# SCH_SnailCard.net
KiCad netlist of a schematic drawn in EasyEDA
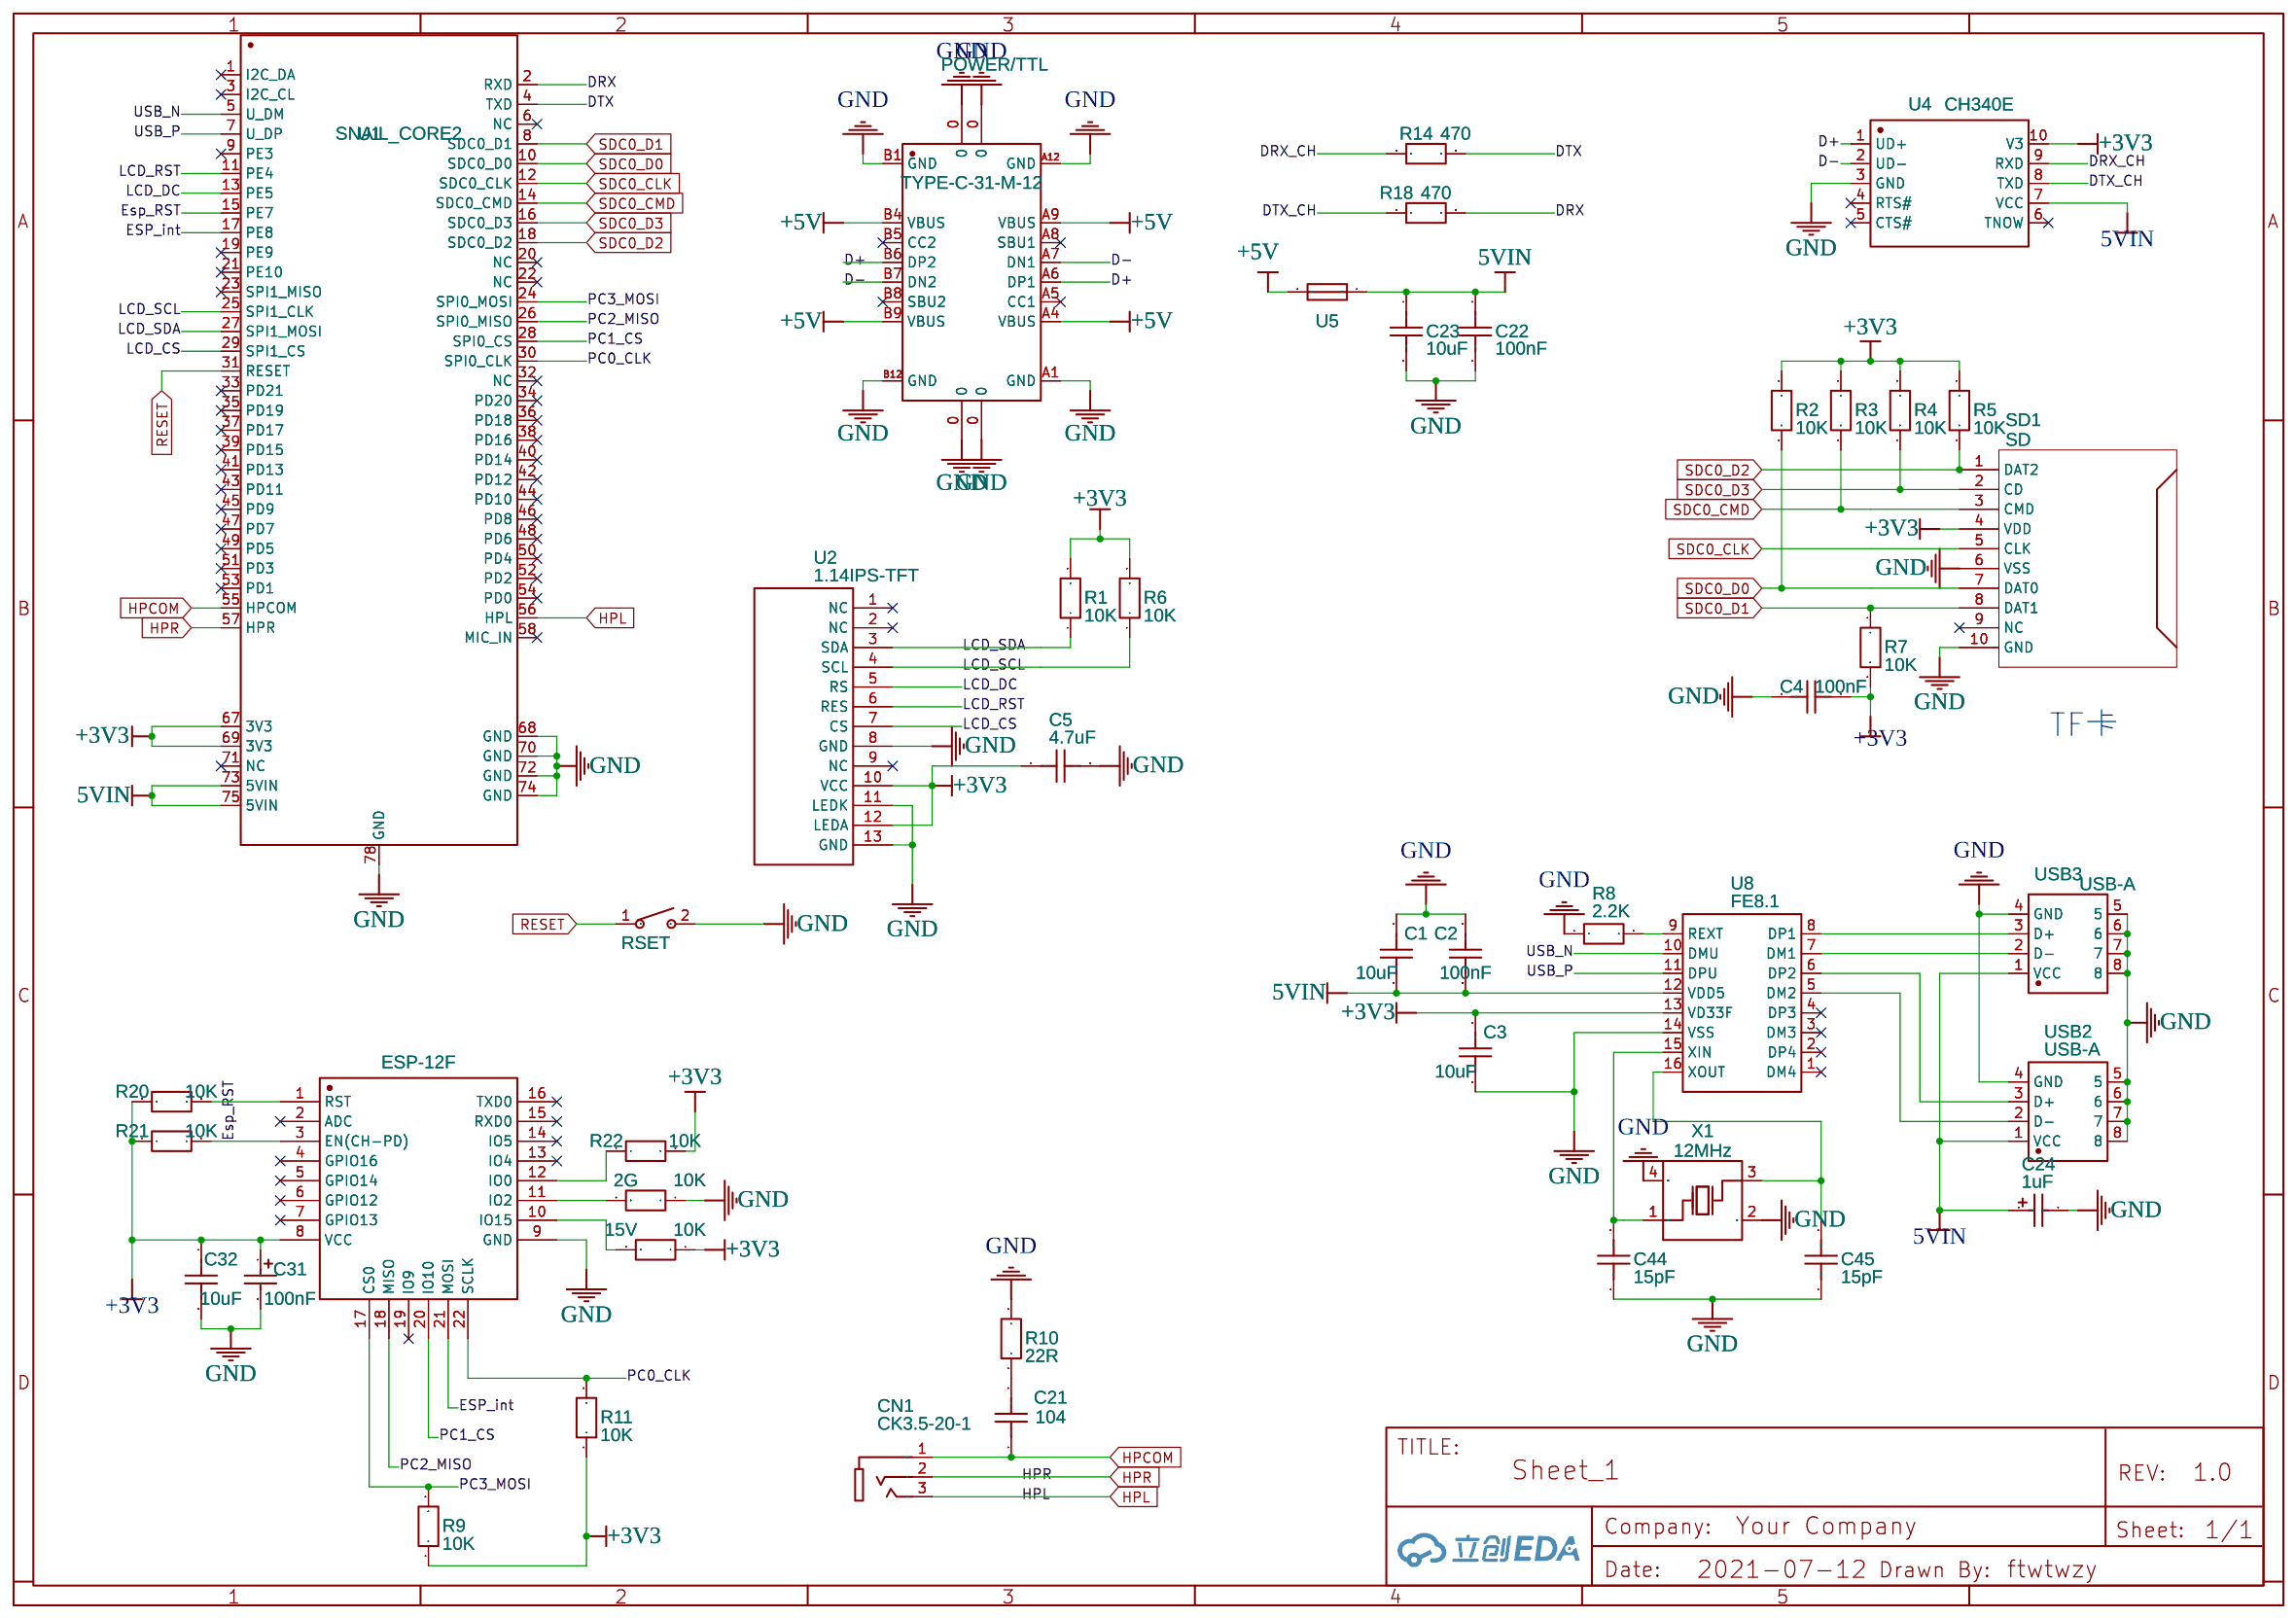
[diagram p0: schematic sheet]

(export (version "E")
  (design (tool "Eeschema 10.0.6"))
  (components
    (comp (ref "2G")
      (value "10K")
      (fields
        (field (name "BOM_Manufacturer Part") "ERA3ARB103V")
        (field (name "BOM_Supplier Part") "C465746")
      )
      (libsource (lib "") (part "ERA3ARB103V_4"))
    )
    (comp (ref "15V")
      (value "10K")
      (fields
        (field (name "BOM_Manufacturer Part") "ERA3ARB103V")
        (field (name "BOM_Supplier Part") "C465746")
      )
      (libsource (lib "") (part "ERA3ARB103V_1"))
    )
    (comp (ref "C1")
      (value "10uF")
      (fields
        (field (name "BOM_Manufacturer Part") "AMK107BJ106MA-T")
        (field (name "BOM_Supplier Part") "C524952")
      )
      (libsource (lib "") (part "AMK107BJ106MA-T"))
    )
    (comp (ref "C2")
      (value "100nF")
      (fields
        (field (name "BOM_Manufacturer Part") "AMK107BJ106MA-T")
        (field (name "BOM_Supplier Part") "C524952")
      )
      (libsource (lib "") (part "AMK107BJ106MA-T"))
    )
    (comp (ref "C3")
      (value "10uF")
      (fields
        (field (name "BOM_Manufacturer Part") "AMK107BJ106MA-T")
        (field (name "BOM_Supplier Part") "C524952")
      )
      (libsource (lib "") (part "AMK107BJ106MA-T"))
    )
    (comp (ref "C4")
      (value "100nF")
      (fields
        (field (name "BOM_Manufacturer Part") "AMK107BJ106MA-T")
        (field (name "BOM_Supplier Part") "C524952")
      )
      (libsource (lib "") (part "AMK107BJ106MA-T_2"))
    )
    (comp (ref "C5")
      (value "4.7uF")
      (fields
        (field (name "BOM_Manufacturer Part") "AMK107BJ106MA-T")
        (field (name "BOM_Supplier Part") "C524952")
      )
      (libsource (lib "") (part "AMK107BJ106MA-T_1"))
    )
    (comp (ref "C21") (value "104") (libsource (lib "") (part "C_0603_US")))
    (comp (ref "C22")
      (value "100nF")
      (fields
        (field (name "BOM_Manufacturer Part") "AMK107BJ106MA-T")
        (field (name "BOM_Supplier Part") "C524952")
      )
      (libsource (lib "") (part "AMK107BJ106MA-T"))
    )
    (comp (ref "C23")
      (value "10uF")
      (fields
        (field (name "BOM_Manufacturer Part") "AMK107BJ106MA-T")
        (field (name "BOM_Supplier Part") "C524952")
      )
      (libsource (lib "") (part "AMK107BJ106MA-T"))
    )
    (comp (ref "C24")
      (value "1uF")
      (fields
        (field (name "BOM_Manufacturer Part") "TAJB105K035RNJ")
        (field (name "BOM_Supplier Part") "C7192")
      )
      (libsource (lib "") (part "TAJB105K035RNJ_1"))
    )
    (comp (ref "C31")
      (value "100nF")
      (fields
        (field (name "BOM_Manufacturer Part") "TAJB105K035RNJ")
        (field (name "BOM_Supplier Part") "C7192")
      )
      (libsource (lib "") (part "TAJB105K035RNJ"))
    )
    (comp (ref "C32")
      (value "10uF")
      (fields
        (field (name "BOM_Manufacturer Part") "AMK107BJ106MA-T")
        (field (name "BOM_Supplier Part") "C524952")
      )
      (libsource (lib "") (part "AMK107BJ106MA-T"))
    )
    (comp (ref "C44") (value "15pF") (libsource (lib "") (part "C_0603_US")))
    (comp (ref "C45") (value "15pF") (libsource (lib "") (part "C_0603_US")))
    (comp (ref "CN1")
      (value "CK3.5-20-1")
      (fields (field (name "BOM_Supplier Part") "C718046"))
      (libsource (lib "") (part "CK3.5-20-1"))
    )
    (comp (ref "POWER/TTL")
      (value "TYPE-C-31-M-12")
      (fields (field (name "BOM_Supplier Part") "C165948"))
      (libsource (lib "") (part "TYPE-C-31-M-12"))
    )
    (comp (ref "R1")
      (value "10K")
      (fields
        (field (name "BOM_Manufacturer Part") "ERA3ARB103V")
        (field (name "BOM_Supplier Part") "C465746")
      )
      (libsource (lib "") (part "ERA3ARB103V"))
    )
    (comp (ref "R2")
      (value "10K")
      (fields
        (field (name "BOM_Manufacturer Part") "ERA3ARB103V")
        (field (name "BOM_Supplier Part") "C465746")
      )
      (libsource (lib "") (part "ERA3ARB103V_2"))
    )
    (comp (ref "R3")
      (value "10K")
      (fields
        (field (name "BOM_Manufacturer Part") "ERA3ARB103V")
        (field (name "BOM_Supplier Part") "C465746")
      )
      (libsource (lib "") (part "ERA3ARB103V_2"))
    )
    (comp (ref "R4")
      (value "10K")
      (fields
        (field (name "BOM_Manufacturer Part") "ERA3ARB103V")
        (field (name "BOM_Supplier Part") "C465746")
      )
      (libsource (lib "") (part "ERA3ARB103V_2"))
    )
    (comp (ref "R5")
      (value "10K")
      (fields
        (field (name "BOM_Manufacturer Part") "ERA3ARB103V")
        (field (name "BOM_Supplier Part") "C465746")
      )
      (libsource (lib "") (part "ERA3ARB103V_2"))
    )
    (comp (ref "R6")
      (value "10K")
      (fields
        (field (name "BOM_Manufacturer Part") "ERA3ARB103V")
        (field (name "BOM_Supplier Part") "C465746")
      )
      (libsource (lib "") (part "ERA3ARB103V"))
    )
    (comp (ref "R7")
      (value "10K")
      (fields
        (field (name "BOM_Manufacturer Part") "ERA3ARB103V")
        (field (name "BOM_Supplier Part") "C465746")
      )
      (libsource (lib "") (part "ERA3ARB103V_2"))
    )
    (comp (ref "R8")
      (value "2.2K")
      (fields
        (field (name "BOM_Manufacturer Part") "ERA3ARB103V")
        (field (name "BOM_Supplier Part") "C465746")
      )
      (libsource (lib "") (part "ERA3ARB103V_3"))
    )
    (comp (ref "R9")
      (value "10K")
      (fields
        (field (name "BOM_Manufacturer Part") "ERA3ARB103V")
        (field (name "BOM_Supplier Part") "C465746")
      )
      (libsource (lib "") (part "ERA3ARB103V"))
    )
    (comp (ref "R10") (value "22R") (libsource (lib "") (part "R_0603_EU")))
    (comp (ref "R11")
      (value "10K")
      (fields
        (field (name "BOM_Manufacturer Part") "ERA3ARB103V")
        (field (name "BOM_Supplier Part") "C465746")
      )
      (libsource (lib "") (part "ERA3ARB103V"))
    )
    (comp (ref "R14")
      (value "470")
      (fields
        (field (name "BOM_Manufacturer Part") "ERA3ARB103V")
        (field (name "BOM_Supplier Part") "C465746")
      )
      (libsource (lib "") (part "ERA3ARB103V_3"))
    )
    (comp (ref "R18")
      (value "470")
      (fields
        (field (name "BOM_Manufacturer Part") "ERA3ARB103V")
        (field (name "BOM_Supplier Part") "C465746")
      )
      (libsource (lib "") (part "ERA3ARB103V_3"))
    )
    (comp (ref "R20")
      (value "10K")
      (fields
        (field (name "BOM_Manufacturer Part") "ERA3ARB103V")
        (field (name "BOM_Supplier Part") "C465746")
      )
      (libsource (lib "") (part "ERA3ARB103V_3"))
    )
    (comp (ref "R21")
      (value "10K")
      (fields
        (field (name "BOM_Manufacturer Part") "ERA3ARB103V")
        (field (name "BOM_Supplier Part") "C465746")
      )
      (libsource (lib "") (part "ERA3ARB103V_3"))
    )
    (comp (ref "R22")
      (value "10K")
      (fields
        (field (name "BOM_Manufacturer Part") "ERA3ARB103V")
        (field (name "BOM_Supplier Part") "C465746")
      )
      (libsource (lib "") (part "ERA3ARB103V_3"))
    )
    (comp (ref "RSET")
      (value "ST-1185S")
      (fields (field (name "BOM_Supplier Part") "C589191"))
      (libsource (lib "") (part "ST-1185S"))
    )
    (comp (ref "SD1") (value "SD") (libsource (lib "") (part "SD")))
    (comp (ref "U1") (value "SNAIL_CORE2") (libsource (lib "") (part "SNAIL_CORE2")))
    (comp (ref "U2") (value "1.14IPS-TFT") (libsource (lib "") (part "1.14IPS-TFT")))
    (comp (ref "U3")
      (value "ESP-12F")
      (fields
        (field (name "BOM_Manufacturer Part") "ESP-12F(ESP8266MOD)")
        (field (name "BOM_Supplier Part") "C82891")
      )
      (libsource (lib "") (part "ESP-12F(ESP8266MOD)"))
    )
    (comp (ref "U4")
      (value "CH340E")
      (fields (field (name "BOM_Supplier Part") "C99652"))
      (libsource (lib "") (part "CH340E"))
    )
    (comp (ref "U5")
      (value "TLC-NSMD005")
      (fields (field (name "BOM_Supplier Part") "C261946"))
      (libsource (lib "") (part "TLC-NSMD005"))
    )
    (comp (ref "U8")
      (value "FE8.1")
      (fields (field (name "BOM_Manufacturer Part") "FE8.1-FSOP16A"))
      (libsource (lib "") (part "FE8.1"))
    )
    (comp (ref "USB2")
      (value "USB-A")
      (fields
        (field (name "BOM_Manufacturer Part") "USB-AF-SMD-12.8X10-H5.7")
        (field (name "BOM_Supplier Part") "C42531")
      )
      (libsource (lib "") (part "USB-A"))
    )
    (comp (ref "USB3")
      (value "USB-A")
      (fields
        (field (name "BOM_Manufacturer Part") "USB-AF-SMD-12.8X10-H5.7")
        (field (name "BOM_Supplier Part") "C42531")
      )
      (libsource (lib "") (part "USB-A"))
    )
    (comp (ref "X1")
      (value "12MHz")
      (fields
        (field (name "BOM_Manufacturer Part") "SMD-3225_4P27.12MHZ20PF10PPM-40&#126;+85℃")
        (field (name "BOM_Supplier Part") "C164053")
      )
      (libsource (lib "") (part "SMD-3225_4P27.12MHZ20PF10PPM-40&#126;+85℃"))
    )
  )
  (nets
    (net (code "1") (name "+3V3") (class "Default")
      (node (ref "15V") (pin "1") (pinfunction "1_1") (pintype "unspecified"))
      (node (ref "C3") (pin "1") (pinfunction "1_1") (pintype "unspecified"))
      (node (ref "C31") (pin "1") (pinfunction "1_1") (pintype "input"))
      (node (ref "C32") (pin "1") (pinfunction "1_1") (pintype "unspecified"))
      (node (ref "C4") (pin "1") (pinfunction "1_1") (pintype "unspecified"))
      (node (ref "C5") (pin "1") (pinfunction "1_1") (pintype "unspecified"))
      (node (ref "R1") (pin "2") (pinfunction "2_2") (pintype "unspecified"))
      (node (ref "R11") (pin "1") (pinfunction "1_1") (pintype "unspecified"))
      (node (ref "R2") (pin "1") (pinfunction "1_1") (pintype "unspecified"))
      (node (ref "R20") (pin "1") (pinfunction "1_1") (pintype "unspecified"))
      (node (ref "R21") (pin "1") (pinfunction "1_1") (pintype "unspecified"))
      (node (ref "R22") (pin "2") (pinfunction "2_2") (pintype "unspecified"))
      (node (ref "R3") (pin "1") (pinfunction "1_1") (pintype "unspecified"))
      (node (ref "R4") (pin "1") (pinfunction "1_1") (pintype "unspecified"))
      (node (ref "R5") (pin "1") (pinfunction "1_1") (pintype "unspecified"))
      (node (ref "R6") (pin "2") (pinfunction "2_2") (pintype "unspecified"))
      (node (ref "R7") (pin "2") (pinfunction "2_2") (pintype "unspecified"))
      (node (ref "R9") (pin "1") (pinfunction "1_1") (pintype "unspecified"))
      (node (ref "SD1") (pin "4") (pinfunction "VDD_4") (pintype "unspecified"))
      (node (ref "U1") (pin "67") (pinfunction "3V3_67") (pintype "unspecified"))
      (node (ref "U1") (pin "69") (pinfunction "3V3_69") (pintype "unspecified"))
      (node (ref "U2") (pin "10") (pinfunction "VCC_10") (pintype "unspecified"))
      (node (ref "U2") (pin "12") (pinfunction "LEDA_12") (pintype "unspecified"))
      (node (ref "U3") (pin "8") (pinfunction "VCC_8") (pintype "unspecified"))
      (node (ref "U4") (pin "10") (pinfunction "V3_10") (pintype "unspecified"))
      (node (ref "U8") (pin "13") (pinfunction "VD33F_13") (pintype "unspecified"))
    )
    (net (code "2") (name "+5V") (class "Default")
      (node (ref "POWER/TTL") (pin "A4") (pinfunction "VBUS_A4") (pintype "unspecified"))
      (node (ref "POWER/TTL") (pin "A9") (pinfunction "VBUS_A9") (pintype "unspecified"))
      (node (ref "POWER/TTL") (pin "B4") (pinfunction "VBUS_B4") (pintype "unspecified"))
      (node (ref "POWER/TTL") (pin "B9") (pinfunction "VBUS_B9") (pintype "unspecified"))
      (node (ref "U5") (pin "2") (pinfunction "2_2") (pintype "unspecified"))
    )
    (net (code "3") (name "/D+") (class "Default")
      (node (ref "POWER/TTL") (pin "A6") (pinfunction "DP1_A6") (pintype "unspecified"))
      (node (ref "POWER/TTL") (pin "B6") (pinfunction "DP2_B6") (pintype "unspecified"))
      (node (ref "U4") (pin "1") (pinfunction "UD+_1") (pintype "unspecified"))
    )
    (net (code "4") (name "/D-") (class "Default")
      (node (ref "POWER/TTL") (pin "A7") (pinfunction "DN1_A7") (pintype "unspecified"))
      (node (ref "POWER/TTL") (pin "B7") (pinfunction "DN2_B7") (pintype "unspecified"))
      (node (ref "U4") (pin "2") (pinfunction "UD-_2") (pintype "unspecified"))
    )
    (net (code "5") (name "/DRX") (class "Default")
      (node (ref "R18") (pin "2") (pinfunction "2_2") (pintype "unspecified"))
      (node (ref "U1") (pin "2") (pinfunction "RXD_2") (pintype "unspecified"))
    )
    (net (code "6") (name "/DRX_CH") (class "Default")
      (node (ref "R14") (pin "1") (pinfunction "1_1") (pintype "unspecified"))
      (node (ref "U4") (pin "9") (pinfunction "RXD_9") (pintype "unspecified"))
    )
    (net (code "7") (name "/DTX") (class "Default")
      (node (ref "R14") (pin "2") (pinfunction "2_2") (pintype "unspecified"))
      (node (ref "U1") (pin "4") (pinfunction "TXD_4") (pintype "unspecified"))
    )
    (net (code "8") (name "/DTX_CH") (class "Default")
      (node (ref "R18") (pin "1") (pinfunction "1_1") (pintype "unspecified"))
      (node (ref "U4") (pin "8") (pinfunction "TXD_8") (pintype "unspecified"))
    )
    (net (code "9") (name "/ESP_int") (class "Default")
      (node (ref "U1") (pin "17") (pinfunction "PE8_17") (pintype "unspecified"))
      (node (ref "U3") (pin "21") (pinfunction "MOSI_21") (pintype "unspecified"))
    )
    (net (code "10") (name "/Esp_RST") (class "Default")
      (node (ref "R21") (pin "2") (pinfunction "2_2") (pintype "unspecified"))
      (node (ref "U1") (pin "15") (pinfunction "PE7_15") (pintype "unspecified"))
      (node (ref "U3") (pin "3") (pinfunction "EN(CH-PD)_3") (pintype "unspecified"))
    )
    (net (code "11") (name "/LCD_CS") (class "Default")
      (node (ref "U1") (pin "29") (pinfunction "SPI1_CS_29") (pintype "unspecified"))
      (node (ref "U2") (pin "7") (pinfunction "CS_7") (pintype "unspecified"))
    )
    (net (code "12") (name "/LCD_DC") (class "Default")
      (node (ref "U1") (pin "13") (pinfunction "PE5_13") (pintype "unspecified"))
      (node (ref "U2") (pin "5") (pinfunction "RS_5") (pintype "unspecified"))
    )
    (net (code "13") (name "/LCD_RST") (class "Default")
      (node (ref "U1") (pin "11") (pinfunction "PE4_11") (pintype "unspecified"))
      (node (ref "U2") (pin "6") (pinfunction "RES_6") (pintype "unspecified"))
    )
    (net (code "14") (name "/LCD_SCL") (class "Default")
      (node (ref "R6") (pin "1") (pinfunction "1_1") (pintype "unspecified"))
      (node (ref "U1") (pin "25") (pinfunction "SPI1_CLK_25") (pintype "unspecified"))
      (node (ref "U2") (pin "4") (pinfunction "SCL_4") (pintype "unspecified"))
    )
    (net (code "15") (name "/LCD_SDA") (class "Default")
      (node (ref "R1") (pin "1") (pinfunction "1_1") (pintype "unspecified"))
      (node (ref "U1") (pin "27") (pinfunction "SPI1_MOSI_27") (pintype "unspecified"))
      (node (ref "U2") (pin "3") (pinfunction "SDA_3") (pintype "unspecified"))
    )
    (net (code "16") (name "/PC0_CLK") (class "Default")
      (node (ref "R11") (pin "2") (pinfunction "2_2") (pintype "unspecified"))
      (node (ref "U1") (pin "30") (pinfunction "SPI0_CLK_30") (pintype "unspecified"))
      (node (ref "U3") (pin "22") (pinfunction "SCLK_22") (pintype "unspecified"))
    )
    (net (code "17") (name "/PC1_CS") (class "Default")
      (node (ref "U1") (pin "28") (pinfunction "SPI0_CS_28") (pintype "unspecified"))
      (node (ref "U3") (pin "20") (pinfunction "IO10_20") (pintype "unspecified"))
    )
    (net (code "18") (name "/PC2_MISO") (class "Default")
      (node (ref "U1") (pin "26") (pinfunction "SPI0_MISO_26") (pintype "unspecified"))
      (node (ref "U3") (pin "18") (pinfunction "MISO_18") (pintype "unspecified"))
    )
    (net (code "19") (name "/PC3_MOSI") (class "Default")
      (node (ref "R9") (pin "2") (pinfunction "2_2") (pintype "unspecified"))
      (node (ref "U1") (pin "24") (pinfunction "SPI0_MOSI_24") (pintype "unspecified"))
      (node (ref "U3") (pin "17") (pinfunction "CS0_17") (pintype "unspecified"))
    )
    (net (code "20") (name "/USB_N") (class "Default")
      (node (ref "U1") (pin "5") (pinfunction "U_DM_5") (pintype "unspecified"))
      (node (ref "U8") (pin "10") (pinfunction "DMU_10") (pintype "unspecified"))
    )
    (net (code "21") (name "/USB_P") (class "Default")
      (node (ref "U1") (pin "7") (pinfunction "U_DP_7") (pintype "unspecified"))
      (node (ref "U8") (pin "11") (pinfunction "DPU_11") (pintype "unspecified"))
    )
    (net (code "22") (name "5VIN") (class "Default")
      (node (ref "C1") (pin "2") (pinfunction "2_2") (pintype "unspecified"))
      (node (ref "C2") (pin "2") (pinfunction "2_2") (pintype "unspecified"))
      (node (ref "C22") (pin "1") (pinfunction "1_1") (pintype "unspecified"))
      (node (ref "C23") (pin "1") (pinfunction "1_1") (pintype "unspecified"))
      (node (ref "C24") (pin "1") (pinfunction "1_1") (pintype "input"))
      (node (ref "U1") (pin "73") (pinfunction "5VIN_73") (pintype "unspecified"))
      (node (ref "U1") (pin "75") (pinfunction "5VIN_75") (pintype "unspecified"))
      (node (ref "U4") (pin "7") (pinfunction "VCC_7") (pintype "unspecified"))
      (node (ref "U5") (pin "1") (pinfunction "1_1") (pintype "unspecified"))
      (node (ref "U8") (pin "12") (pinfunction "VDD5_12") (pintype "unspecified"))
      (node (ref "USB2") (pin "1") (pinfunction "VCC_1") (pintype "unspecified"))
      (node (ref "USB3") (pin "1") (pinfunction "VCC_1") (pintype "unspecified"))
    )
    (net (code "23") (name "GND") (class "Default")
      (node (ref "2G") (pin "1") (pinfunction "1_1") (pintype "unspecified"))
      (node (ref "C1") (pin "1") (pinfunction "1_1") (pintype "unspecified"))
      (node (ref "C2") (pin "1") (pinfunction "1_1") (pintype "unspecified"))
      (node (ref "C22") (pin "2") (pinfunction "2_2") (pintype "unspecified"))
      (node (ref "C23") (pin "2") (pinfunction "2_2") (pintype "unspecified"))
      (node (ref "C24") (pin "2") (pinfunction "2_2") (pintype "input"))
      (node (ref "C3") (pin "2") (pinfunction "2_2") (pintype "unspecified"))
      (node (ref "C31") (pin "2") (pinfunction "2_2") (pintype "input"))
      (node (ref "C32") (pin "2") (pinfunction "2_2") (pintype "unspecified"))
      (node (ref "C4") (pin "2") (pinfunction "2_2") (pintype "unspecified"))
      (node (ref "C44") (pin "1") (pinfunction "1_1") (pintype "unspecified"))
      (node (ref "C45") (pin "1") (pinfunction "1_1") (pintype "unspecified"))
      (node (ref "C5") (pin "2") (pinfunction "2_2") (pintype "unspecified"))
      (node (ref "POWER/TTL") (pin "0") (pinfunction "0_0") (pintype "unspecified"))
      (node (ref "POWER/TTL") (pin "A1") (pinfunction "GND_A1") (pintype "unspecified"))
      (node (ref "POWER/TTL") (pin "A12") (pinfunction "GND_A12") (pintype "unspecified"))
      (node (ref "POWER/TTL") (pin "B1") (pinfunction "GND_B1") (pintype "unspecified"))
      (node (ref "POWER/TTL") (pin "B12") (pinfunction "GND_B12") (pintype "unspecified"))
      (node (ref "R10") (pin "2") (pinfunction "2_2") (pintype "unspecified"))
      (node (ref "R8") (pin "1") (pinfunction "1_1") (pintype "unspecified"))
      (node (ref "RSET") (pin "2") (pinfunction "2_2") (pintype "unspecified"))
      (node (ref "SD1") (pin "10") (pinfunction "GND_10") (pintype "unspecified"))
      (node (ref "SD1") (pin "6") (pinfunction "VSS_6") (pintype "unspecified"))
      (node (ref "U1") (pin "68") (pinfunction "GND_68") (pintype "unspecified"))
      (node (ref "U1") (pin "70") (pinfunction "GND_70") (pintype "unspecified"))
      (node (ref "U1") (pin "72") (pinfunction "GND_72") (pintype "unspecified"))
      (node (ref "U1") (pin "74") (pinfunction "GND_74") (pintype "unspecified"))
      (node (ref "U1") (pin "78") (pinfunction "GND_78") (pintype "unspecified"))
      (node (ref "U2") (pin "11") (pinfunction "LEDK_11") (pintype "unspecified"))
      (node (ref "U2") (pin "13") (pinfunction "GND_13") (pintype "unspecified"))
      (node (ref "U2") (pin "8") (pinfunction "GND_8") (pintype "unspecified"))
      (node (ref "U3") (pin "9") (pinfunction "GND_9") (pintype "unspecified"))
      (node (ref "U4") (pin "3") (pinfunction "GND_3") (pintype "unspecified"))
      (node (ref "U8") (pin "14") (pinfunction "VSS_14") (pintype "unspecified"))
      (node (ref "USB2") (pin "4") (pinfunction "GND_4") (pintype "unspecified"))
      (node (ref "USB2") (pin "5") (pinfunction "5_5") (pintype "unspecified"))
      (node (ref "USB2") (pin "6") (pinfunction "6_6") (pintype "unspecified"))
      (node (ref "USB2") (pin "7") (pinfunction "7_7") (pintype "unspecified"))
      (node (ref "USB2") (pin "8") (pinfunction "8_8") (pintype "unspecified"))
      (node (ref "USB3") (pin "4") (pinfunction "GND_4") (pintype "unspecified"))
      (node (ref "USB3") (pin "5") (pinfunction "5_5") (pintype "unspecified"))
      (node (ref "USB3") (pin "6") (pinfunction "6_6") (pintype "unspecified"))
      (node (ref "USB3") (pin "7") (pinfunction "7_7") (pintype "unspecified"))
      (node (ref "USB3") (pin "8") (pinfunction "8_8") (pintype "unspecified"))
      (node (ref "X1") (pin "2") (pinfunction "GND_2") (pintype "unspecified"))
      (node (ref "X1") (pin "4") (pinfunction "GND_4") (pintype "unspecified"))
    )
    (net (code "24") (name "HPCOM") (class "Default")
      (node (ref "C21") (pin "1") (pinfunction "1_1") (pintype "unspecified"))
      (node (ref "CN1") (pin "1") (pinfunction "1_1") (pintype "unspecified"))
      (node (ref "U1") (pin "55") (pinfunction "HPCOM_55") (pintype "unspecified"))
    )
    (net (code "25") (name "HPL") (class "Default")
      (node (ref "CN1") (pin "3") (pinfunction "3_3") (pintype "unspecified"))
      (node (ref "U1") (pin "56") (pinfunction "HPL_56") (pintype "unspecified"))
    )
    (net (code "26") (name "HPR") (class "Default")
      (node (ref "CN1") (pin "2") (pinfunction "2_2") (pintype "unspecified"))
      (node (ref "U1") (pin "57") (pinfunction "HPR_57") (pintype "unspecified"))
    )
    (net (code "27") (name "Net-(C21-Pad2)") (class "Default")
      (node (ref "C21") (pin "2") (pinfunction "2_2") (pintype "unspecified"))
      (node (ref "R10") (pin "1") (pinfunction "1_1") (pintype "unspecified"))
    )
    (net (code "28") (name "Net-(U3-IO0)") (class "Default")
      (node (ref "R22") (pin "1") (pinfunction "1_1") (pintype "unspecified"))
      (node (ref "U3") (pin "12") (pinfunction "IO0_12") (pintype "unspecified"))
    )
    (net (code "29") (name "Net-(U3-IO2)") (class "Default")
      (node (ref "2G") (pin "2") (pinfunction "2_2") (pintype "unspecified"))
      (node (ref "U3") (pin "11") (pinfunction "IO2_11") (pintype "unspecified"))
    )
    (net (code "30") (name "Net-(U3-IO15)") (class "Default")
      (node (ref "15V") (pin "2") (pinfunction "2_2") (pintype "unspecified"))
      (node (ref "U3") (pin "10") (pinfunction "IO15_10") (pintype "unspecified"))
    )
    (net (code "31") (name "Net-(U3-RST)") (class "Default")
      (node (ref "R20") (pin "2") (pinfunction "2_2") (pintype "unspecified"))
      (node (ref "U3") (pin "1") (pinfunction "RST_1") (pintype "unspecified"))
    )
    (net (code "32") (name "Net-(U8-DM1)") (class "Default")
      (node (ref "U8") (pin "7") (pinfunction "DM1_7") (pintype "unspecified"))
      (node (ref "USB3") (pin "2") (pinfunction "D-_2") (pintype "unspecified"))
    )
    (net (code "33") (name "Net-(U8-DM2)") (class "Default")
      (node (ref "U8") (pin "5") (pinfunction "DM2_5") (pintype "unspecified"))
      (node (ref "USB2") (pin "2") (pinfunction "D-_2") (pintype "unspecified"))
    )
    (net (code "34") (name "Net-(U8-DP1)") (class "Default")
      (node (ref "U8") (pin "8") (pinfunction "DP1_8") (pintype "unspecified"))
      (node (ref "USB3") (pin "3") (pinfunction "D+_3") (pintype "unspecified"))
    )
    (net (code "35") (name "Net-(U8-DP2)") (class "Default")
      (node (ref "U8") (pin "6") (pinfunction "DP2_6") (pintype "unspecified"))
      (node (ref "USB2") (pin "3") (pinfunction "D+_3") (pintype "unspecified"))
    )
    (net (code "36") (name "Net-(U8-REXT)") (class "Default")
      (node (ref "R8") (pin "2") (pinfunction "2_2") (pintype "unspecified"))
      (node (ref "U8") (pin "9") (pinfunction "REXT_9") (pintype "unspecified"))
    )
    (net (code "37") (name "Net-(U8-XIN)") (class "Default")
      (node (ref "C44") (pin "2") (pinfunction "2_2") (pintype "unspecified"))
      (node (ref "U8") (pin "15") (pinfunction "XIN_15") (pintype "unspecified"))
      (node (ref "X1") (pin "1") (pinfunction "OSC1_1") (pintype "unspecified"))
    )
    (net (code "38") (name "Net-(U8-XOUT)") (class "Default")
      (node (ref "C45") (pin "2") (pinfunction "2_2") (pintype "unspecified"))
      (node (ref "U8") (pin "16") (pinfunction "XOUT_16") (pintype "unspecified"))
      (node (ref "X1") (pin "3") (pinfunction "OSC2_3") (pintype "unspecified"))
    )
    (net (code "39") (name "RESET") (class "Default")
      (node (ref "RSET") (pin "1") (pinfunction "1_1") (pintype "unspecified"))
      (node (ref "U1") (pin "31") (pinfunction "RESET_31") (pintype "unspecified"))
    )
    (net (code "40") (name "SDC0_CLK") (class "Default")
      (node (ref "SD1") (pin "5") (pinfunction "CLK_5") (pintype "unspecified"))
      (node (ref "U1") (pin "12") (pinfunction "SDC0_CLK_12") (pintype "unspecified"))
    )
    (net (code "41") (name "SDC0_CMD") (class "Default")
      (node (ref "R3") (pin "2") (pinfunction "2_2") (pintype "unspecified"))
      (node (ref "SD1") (pin "3") (pinfunction "CMD_3") (pintype "unspecified"))
      (node (ref "U1") (pin "14") (pinfunction "SDC0_CMD_14") (pintype "unspecified"))
    )
    (net (code "42") (name "SDC0_D0") (class "Default")
      (node (ref "R2") (pin "2") (pinfunction "2_2") (pintype "unspecified"))
      (node (ref "SD1") (pin "7") (pinfunction "DAT0_7") (pintype "unspecified"))
      (node (ref "U1") (pin "10") (pinfunction "SDC0_D0_10") (pintype "unspecified"))
    )
    (net (code "43") (name "SDC0_D1") (class "Default")
      (node (ref "R7") (pin "1") (pinfunction "1_1") (pintype "unspecified"))
      (node (ref "SD1") (pin "8") (pinfunction "DAT1_8") (pintype "unspecified"))
      (node (ref "U1") (pin "8") (pinfunction "SDC0_D1_8") (pintype "unspecified"))
    )
    (net (code "44") (name "SDC0_D2") (class "Default")
      (node (ref "R5") (pin "2") (pinfunction "2_2") (pintype "unspecified"))
      (node (ref "SD1") (pin "1") (pinfunction "DAT2_1") (pintype "unspecified"))
      (node (ref "U1") (pin "18") (pinfunction "SDC0_D2_18") (pintype "unspecified"))
    )
    (net (code "45") (name "SDC0_D3") (class "Default")
      (node (ref "R4") (pin "2") (pinfunction "2_2") (pintype "unspecified"))
      (node (ref "SD1") (pin "2") (pinfunction "CD_2") (pintype "unspecified"))
      (node (ref "U1") (pin "16") (pinfunction "SDC0_D3_16") (pintype "unspecified"))
    )
    (net (code "46") (name "unconnected-(POWER/TTL-CC1-PadA5)") (class "Default")
      (node (ref "POWER/TTL") (pin "A5") (pinfunction "CC1_A5") (pintype "unspecified+no_connect"))
    )
    (net (code "47") (name "unconnected-(POWER/TTL-CC2-PadB5)") (class "Default")
      (node (ref "POWER/TTL") (pin "B5") (pinfunction "CC2_B5") (pintype "unspecified+no_connect"))
    )
    (net (code "48") (name "unconnected-(POWER/TTL-SBU1-PadA8)") (class "Default")
      (node (ref "POWER/TTL") (pin "A8") (pinfunction "SBU1_A8") (pintype "unspecified+no_connect"))
    )
    (net (code "49") (name "unconnected-(POWER/TTL-SBU2-PadB8)") (class "Default")
      (node (ref "POWER/TTL") (pin "B8") (pinfunction "SBU2_B8") (pintype "unspecified+no_connect"))
    )
    (net (code "50") (name "unconnected-(SD1-NC-Pad9)") (class "Default")
      (node (ref "SD1") (pin "9") (pinfunction "NC_9") (pintype "unspecified+no_connect"))
    )
    (net (code "51") (name "unconnected-(U1-I2C_CL-Pad3)") (class "Default")
      (node (ref "U1") (pin "3") (pinfunction "I2C_CL_3") (pintype "unspecified+no_connect"))
    )
    (net (code "52") (name "unconnected-(U1-I2C_DA-Pad1)") (class "Default")
      (node (ref "U1") (pin "1") (pinfunction "I2C_DA_1") (pintype "unspecified+no_connect"))
    )
    (net (code "53") (name "unconnected-(U1-MIC_IN-Pad58)") (class "Default")
      (node (ref "U1") (pin "58") (pinfunction "MIC_IN_58") (pintype "unspecified+no_connect"))
    )
    (net (code "54") (name "unconnected-(U1-NC-Pad6)") (class "Default")
      (node (ref "U1") (pin "6") (pinfunction "NC_6") (pintype "unspecified+no_connect"))
    )
    (net (code "55") (name "unconnected-(U1-NC-Pad20)") (class "Default")
      (node (ref "U1") (pin "20") (pinfunction "NC_20") (pintype "unspecified+no_connect"))
    )
    (net (code "56") (name "unconnected-(U1-NC-Pad22)") (class "Default")
      (node (ref "U1") (pin "22") (pinfunction "NC_22") (pintype "unspecified+no_connect"))
    )
    (net (code "57") (name "unconnected-(U1-NC-Pad32)") (class "Default")
      (node (ref "U1") (pin "32") (pinfunction "NC_32") (pintype "unspecified+no_connect"))
    )
    (net (code "58") (name "unconnected-(U1-NC-Pad71)") (class "Default")
      (node (ref "U1") (pin "71") (pinfunction "NC_71") (pintype "unspecified+no_connect"))
    )
    (net (code "59") (name "unconnected-(U1-PD0-Pad54)") (class "Default")
      (node (ref "U1") (pin "54") (pinfunction "PD0_54") (pintype "unspecified+no_connect"))
    )
    (net (code "60") (name "unconnected-(U1-PD1-Pad53)") (class "Default")
      (node (ref "U1") (pin "53") (pinfunction "PD1_53") (pintype "unspecified+no_connect"))
    )
    (net (code "61") (name "unconnected-(U1-PD2-Pad52)") (class "Default")
      (node (ref "U1") (pin "52") (pinfunction "PD2_52") (pintype "unspecified+no_connect"))
    )
    (net (code "62") (name "unconnected-(U1-PD3-Pad51)") (class "Default")
      (node (ref "U1") (pin "51") (pinfunction "PD3_51") (pintype "unspecified+no_connect"))
    )
    (net (code "63") (name "unconnected-(U1-PD4-Pad50)") (class "Default")
      (node (ref "U1") (pin "50") (pinfunction "PD4_50") (pintype "unspecified+no_connect"))
    )
    (net (code "64") (name "unconnected-(U1-PD5-Pad49)") (class "Default")
      (node (ref "U1") (pin "49") (pinfunction "PD5_49") (pintype "unspecified+no_connect"))
    )
    (net (code "65") (name "unconnected-(U1-PD6-Pad48)") (class "Default")
      (node (ref "U1") (pin "48") (pinfunction "PD6_48") (pintype "unspecified+no_connect"))
    )
    (net (code "66") (name "unconnected-(U1-PD7-Pad47)") (class "Default")
      (node (ref "U1") (pin "47") (pinfunction "PD7_47") (pintype "unspecified+no_connect"))
    )
    (net (code "67") (name "unconnected-(U1-PD8-Pad46)") (class "Default")
      (node (ref "U1") (pin "46") (pinfunction "PD8_46") (pintype "unspecified+no_connect"))
    )
    (net (code "68") (name "unconnected-(U1-PD9-Pad45)") (class "Default")
      (node (ref "U1") (pin "45") (pinfunction "PD9_45") (pintype "unspecified+no_connect"))
    )
    (net (code "69") (name "unconnected-(U1-PD10-Pad44)") (class "Default")
      (node (ref "U1") (pin "44") (pinfunction "PD10_44") (pintype "unspecified+no_connect"))
    )
    (net (code "70") (name "unconnected-(U1-PD11-Pad43)") (class "Default")
      (node (ref "U1") (pin "43") (pinfunction "PD11_43") (pintype "unspecified+no_connect"))
    )
    (net (code "71") (name "unconnected-(U1-PD12-Pad42)") (class "Default")
      (node (ref "U1") (pin "42") (pinfunction "PD12_42") (pintype "unspecified+no_connect"))
    )
    (net (code "72") (name "unconnected-(U1-PD13-Pad41)") (class "Default")
      (node (ref "U1") (pin "41") (pinfunction "PD13_41") (pintype "unspecified+no_connect"))
    )
    (net (code "73") (name "unconnected-(U1-PD14-Pad40)") (class "Default")
      (node (ref "U1") (pin "40") (pinfunction "PD14_40") (pintype "unspecified+no_connect"))
    )
    (net (code "74") (name "unconnected-(U1-PD15-Pad39)") (class "Default")
      (node (ref "U1") (pin "39") (pinfunction "PD15_39") (pintype "unspecified+no_connect"))
    )
    (net (code "75") (name "unconnected-(U1-PD16-Pad38)") (class "Default")
      (node (ref "U1") (pin "38") (pinfunction "PD16_38") (pintype "unspecified+no_connect"))
    )
    (net (code "76") (name "unconnected-(U1-PD17-Pad37)") (class "Default")
      (node (ref "U1") (pin "37") (pinfunction "PD17_37") (pintype "unspecified+no_connect"))
    )
    (net (code "77") (name "unconnected-(U1-PD18-Pad36)") (class "Default")
      (node (ref "U1") (pin "36") (pinfunction "PD18_36") (pintype "unspecified+no_connect"))
    )
    (net (code "78") (name "unconnected-(U1-PD19-Pad35)") (class "Default")
      (node (ref "U1") (pin "35") (pinfunction "PD19_35") (pintype "unspecified+no_connect"))
    )
    (net (code "79") (name "unconnected-(U1-PD20-Pad34)") (class "Default")
      (node (ref "U1") (pin "34") (pinfunction "PD20_34") (pintype "unspecified+no_connect"))
    )
    (net (code "80") (name "unconnected-(U1-PD21-Pad33)") (class "Default")
      (node (ref "U1") (pin "33") (pinfunction "PD21_33") (pintype "unspecified+no_connect"))
    )
    (net (code "81") (name "unconnected-(U1-PE3-Pad9)") (class "Default")
      (node (ref "U1") (pin "9") (pinfunction "PE3_9") (pintype "unspecified+no_connect"))
    )
    (net (code "82") (name "unconnected-(U1-PE9-Pad19)") (class "Default")
      (node (ref "U1") (pin "19") (pinfunction "PE9_19") (pintype "unspecified+no_connect"))
    )
    (net (code "83") (name "unconnected-(U1-PE10-Pad21)") (class "Default")
      (node (ref "U1") (pin "21") (pinfunction "PE10_21") (pintype "unspecified+no_connect"))
    )
    (net (code "84") (name "unconnected-(U1-SPI1_MISO-Pad23)") (class "Default")
      (node (ref "U1") (pin "23") (pinfunction "SPI1_MISO_23") (pintype "unspecified+no_connect"))
    )
    (net (code "85") (name "unconnected-(U2-NC-Pad1)") (class "Default")
      (node (ref "U2") (pin "1") (pinfunction "NC_1") (pintype "unspecified+no_connect"))
    )
    (net (code "86") (name "unconnected-(U2-NC-Pad2)") (class "Default")
      (node (ref "U2") (pin "2") (pinfunction "NC_2") (pintype "unspecified+no_connect"))
    )
    (net (code "87") (name "unconnected-(U2-NC-Pad9)") (class "Default")
      (node (ref "U2") (pin "9") (pinfunction "NC_9") (pintype "unspecified+no_connect"))
    )
    (net (code "88") (name "unconnected-(U3-ADC-Pad2)") (class "Default")
      (node (ref "U3") (pin "2") (pinfunction "ADC_2") (pintype "unspecified+no_connect"))
    )
    (net (code "89") (name "unconnected-(U3-GPIO12-Pad6)") (class "Default")
      (node (ref "U3") (pin "6") (pinfunction "GPIO12_6") (pintype "unspecified+no_connect"))
    )
    (net (code "90") (name "unconnected-(U3-GPIO13-Pad7)") (class "Default")
      (node (ref "U3") (pin "7") (pinfunction "GPIO13_7") (pintype "unspecified+no_connect"))
    )
    (net (code "91") (name "unconnected-(U3-GPIO14-Pad5)") (class "Default")
      (node (ref "U3") (pin "5") (pinfunction "GPIO14_5") (pintype "unspecified+no_connect"))
    )
    (net (code "92") (name "unconnected-(U3-GPIO16-Pad4)") (class "Default")
      (node (ref "U3") (pin "4") (pinfunction "GPIO16_4") (pintype "unspecified+no_connect"))
    )
    (net (code "93") (name "unconnected-(U3-IO4-Pad13)") (class "Default")
      (node (ref "U3") (pin "13") (pinfunction "IO4_13") (pintype "unspecified+no_connect"))
    )
    (net (code "94") (name "unconnected-(U3-IO5-Pad14)") (class "Default")
      (node (ref "U3") (pin "14") (pinfunction "IO5_14") (pintype "unspecified+no_connect"))
    )
    (net (code "95") (name "unconnected-(U3-IO9-Pad19)") (class "Default")
      (node (ref "U3") (pin "19") (pinfunction "IO9_19") (pintype "unspecified+no_connect"))
    )
    (net (code "96") (name "unconnected-(U3-RXD0-Pad15)") (class "Default")
      (node (ref "U3") (pin "15") (pinfunction "RXD0_15") (pintype "unspecified+no_connect"))
    )
    (net (code "97") (name "unconnected-(U3-TXD0-Pad16)") (class "Default")
      (node (ref "U3") (pin "16") (pinfunction "TXD0_16") (pintype "unspecified+no_connect"))
    )
    (net (code "98") (name "unconnected-(U4-CTS#-Pad5)") (class "Default")
      (node (ref "U4") (pin "5") (pinfunction "CTS#_5") (pintype "unspecified+no_connect"))
    )
    (net (code "99") (name "unconnected-(U4-RTS#-Pad4)") (class "Default")
      (node (ref "U4") (pin "4") (pinfunction "RTS#_4") (pintype "unspecified+no_connect"))
    )
    (net (code "100") (name "unconnected-(U4-TNOW-Pad6)") (class "Default")
      (node (ref "U4") (pin "6") (pinfunction "TNOW_6") (pintype "unspecified+no_connect"))
    )
    (net (code "101") (name "unconnected-(U8-DM3-Pad3)") (class "Default")
      (node (ref "U8") (pin "3") (pinfunction "DM3_3") (pintype "unspecified+no_connect"))
    )
    (net (code "102") (name "unconnected-(U8-DM4-Pad1)") (class "Default")
      (node (ref "U8") (pin "1") (pinfunction "DM4_1") (pintype "unspecified+no_connect"))
    )
    (net (code "103") (name "unconnected-(U8-DP3-Pad4)") (class "Default")
      (node (ref "U8") (pin "4") (pinfunction "DP3_4") (pintype "unspecified+no_connect"))
    )
    (net (code "104") (name "unconnected-(U8-DP4-Pad2)") (class "Default")
      (node (ref "U8") (pin "2") (pinfunction "DP4_2") (pintype "unspecified+no_connect"))
    )
  )
)
